# led.net
KiCad netlist of a schematic drawn in Altium Designer
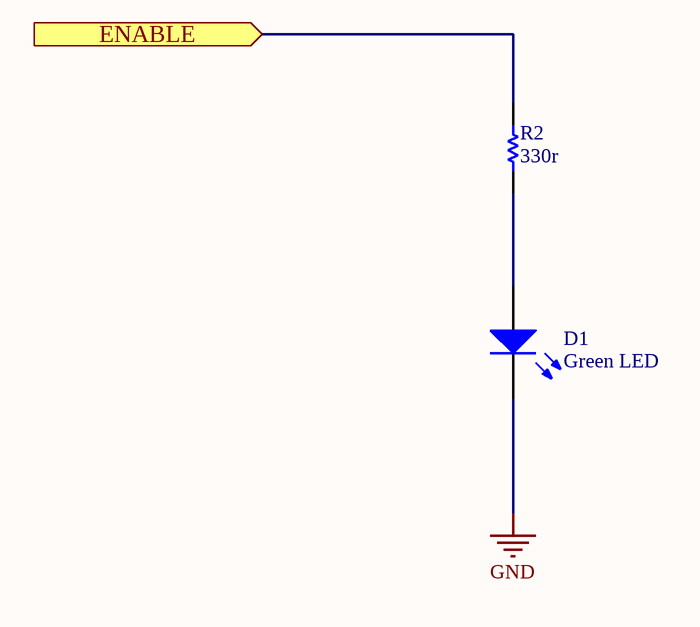
[diagram p0: led.SchDoc]

(export (version "E")
  (design (tool "Eeschema 10.0.6"))
  (components
    (comp (ref "D1")
      (value "Green LED")
      (footprint "PcbLib_2:LED 0805")
      (description "Typical INFRARED GaAs LED")
      (fields (field (name "PUBLISHER") "Altium Limited"))
      (libsource (lib "Miscellaneous Devices") (part "LED0"))
    )
    (comp (ref "R2")
      (value "330r")
      (footprint "PcbLib_2:RESC1608n")
      (description "Resistor")
      (fields (field (name "PUBLISHER") "Altium Limited"))
      (libsource (lib "Miscellaneous Devices") (part "Res1"))
    )
  )
  (nets
    (net (code "1") (name "/ENABLE") (class "Default")
      (node (ref "R2") (pin "2") (pinfunction "2_2") (pintype "passive"))
    )
    (net (code "2") (name "GND") (class "Default")
      (node (ref "D1") (pin "2") (pinfunction "K_2") (pintype "passive"))
    )
    (net (code "3") (name "Net-(D1-A)") (class "Default")
      (node (ref "D1") (pin "1") (pinfunction "A_1") (pintype "passive"))
      (node (ref "R2") (pin "1") (pinfunction "1_1") (pintype "passive"))
    )
  )
)
